# light_sensor_basic.net
KiCad netlist of a schematic drawn in EAGLE
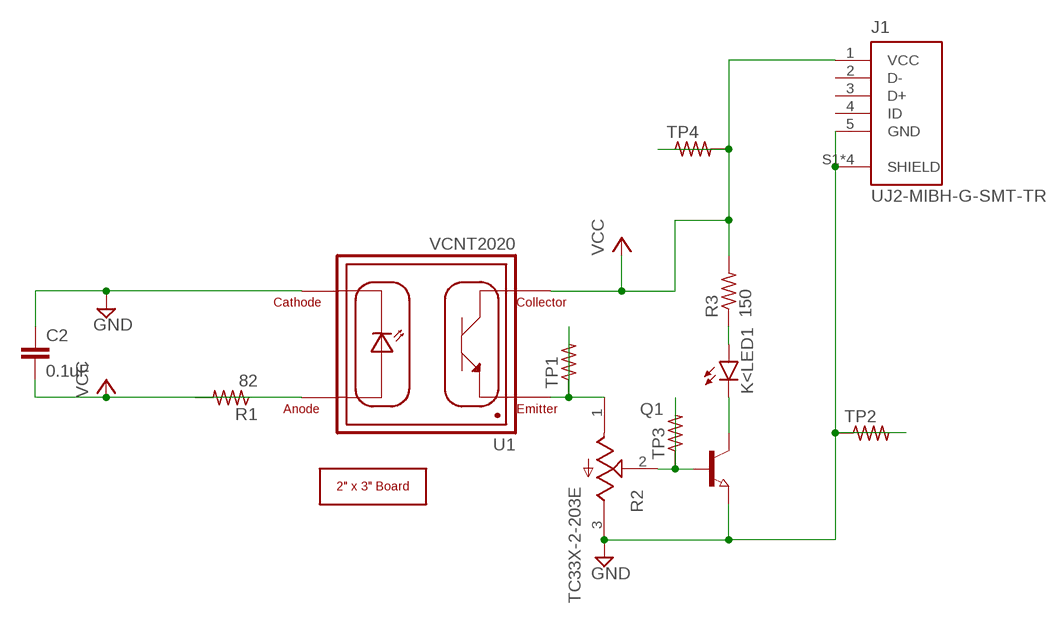
[diagram p0: schematic, sheet 1]

(export (version "E")
  (design (tool "Eeschema 10.0.6"))
  (components
    (comp (ref "C2")
      (value "0.1uF")
      (footprint "eagle-import:C1206")
      (libsource (lib "eagle-import") (part "C-EUC1206"))
    )
    (comp (ref "J1")
      (value "UJ2-MIBH-G-SMT-TR")
      (footprint "eagle-import:CUI_UJ2-MIBH-G-SMT-TR")
      (fields (field (name "MANUFACTURER") "CUI"))
      (libsource (lib "eagle-import") (part "UJ2-MIBH-G-SMT-TR"))
    )
    (comp (ref "K<LED1")
      (value "LEDCHIPLED_0805")
      (footprint "eagle-import:CHIPLED_0805")
      (libsource (lib "eagle-import") (part "LEDCHIPLED_0805"))
    )
    (comp (ref "Q1")
      (value "NPN-TRANSISTOR_SOT23")
      (footprint "eagle-import:SOT23")
      (libsource (lib "eagle-import") (part "NPN-TRANSISTOR_SOT23"))
    )
    (comp (ref "R1")
      (value "82")
      (footprint "eagle-import:R1206")
      (libsource (lib "eagle-import") (part "R-US_R1206"))
    )
    (comp (ref "R2")
      (value "TC33X-2-203E")
      (footprint "eagle-import:TRIM_TC33X-2-203E")
      (fields (field (name "DIGIKEY_PART_NUMBER") "TC33X-2-203ETR-ND") (field (name "MF") "Bourns"))
      (libsource (lib "eagle-import") (part "TC33X-2-203E"))
    )
    (comp (ref "R3")
      (value "150")
      (footprint "eagle-import:R0805")
      (libsource (lib "eagle-import") (part "R-US_R0805"))
    )
    (comp (ref "TP1")
      (value "R-US_R1206")
      (footprint "eagle-import:R1206")
      (libsource (lib "eagle-import") (part "R-US_R1206"))
    )
    (comp (ref "TP2")
      (value "R-US_R1206")
      (footprint "eagle-import:R1206")
      (libsource (lib "eagle-import") (part "R-US_R1206"))
    )
    (comp (ref "TP3")
      (value "R-US_R1206")
      (footprint "eagle-import:R1206")
      (libsource (lib "eagle-import") (part "R-US_R1206"))
    )
    (comp (ref "TP4")
      (value "R-US_R1206")
      (footprint "eagle-import:R1206")
      (libsource (lib "eagle-import") (part "R-US_R1206"))
    )
    (comp (ref "U$1")
      (value "2X3_BOARD_V2")
      (footprint "eagle-import:2X3_BOARD_V2")
      (libsource (lib "eagle-import") (part "2X3_BOARD_V2"))
    )
    (comp (ref "U1")
      (value "VCNT2020")
      (footprint "eagle-import:XDCR_VCNT2020")
      (fields (field (name "DIGIKEY_PART_NUMBER") "VCNT2020TR-ND") (field (name "MF") "Vishay"))
      (libsource (lib "eagle-import") (part "VCNT2020"))
    )
  )
  (nets
    (net (code "1") (name "GND") (class "Default")
      (node (ref "C2") (pin "1") (pinfunction "1_1") (pintype "passive"))
      (node (ref "J1") (pin "5") (pinfunction "GND_5") (pintype "power_in"))
      (node (ref "J1") (pin "S1") (pinfunction "SHIELD_S1") (pintype "passive"))
      (node (ref "J1") (pin "S2") (pinfunction "SHIELD_S2") (pintype "passive"))
      (node (ref "J1") (pin "S3") (pinfunction "SHIELD_S3") (pintype "passive"))
      (node (ref "J1") (pin "S4") (pinfunction "SHIELD_S4") (pintype "passive"))
      (node (ref "Q1") (pin "2") (pinfunction "E_2") (pintype "passive"))
      (node (ref "R2") (pin "3") (pinfunction "CW_3") (pintype "passive"))
      (node (ref "TP2") (pin "1") (pinfunction "1_1") (pintype "passive"))
      (node (ref "TP2") (pin "2") (pinfunction "2_2") (pintype "passive"))
      (node (ref "U1") (pin "4") (pinfunction "CATHODE_4") (pintype "passive"))
    )
    (net (code "2") (name "Net-(K<LED1-PadA)") (class "Default")
      (node (ref "K<LED1") (pin "A") (pinfunction "A_A") (pintype "passive"))
      (node (ref "R3") (pin "1") (pinfunction "1_1") (pintype "passive"))
    )
    (net (code "3") (name "Net-(Q1-B)") (class "Default")
      (node (ref "Q1") (pin "1") (pinfunction "B_1") (pintype "passive"))
      (node (ref "R2") (pin "2") (pinfunction "W_2") (pintype "passive"))
      (node (ref "TP3") (pin "1") (pinfunction "1_1") (pintype "passive"))
      (node (ref "TP3") (pin "2") (pinfunction "2_2") (pintype "passive"))
    )
    (net (code "4") (name "Net-(Q1-C)") (class "Default")
      (node (ref "K<LED1") (pin "C") (pinfunction "C_C") (pintype "passive"))
      (node (ref "Q1") (pin "3") (pinfunction "C_3") (pintype "passive"))
    )
    (net (code "5") (name "Net-(R2-CCW)") (class "Default")
      (node (ref "R2") (pin "1") (pinfunction "CCW_1") (pintype "passive"))
      (node (ref "TP1") (pin "1") (pinfunction "1_1") (pintype "passive"))
      (node (ref "TP1") (pin "2") (pinfunction "2_2") (pintype "passive"))
      (node (ref "U1") (pin "1") (pinfunction "EMITTER_1") (pintype "passive"))
    )
    (net (code "6") (name "Net-(U1-ANODE)") (class "Default")
      (node (ref "R1") (pin "2") (pinfunction "2_2") (pintype "passive"))
      (node (ref "U1") (pin "3") (pinfunction "ANODE_3") (pintype "passive"))
    )
    (net (code "7") (name "VCC") (class "Default")
      (node (ref "C2") (pin "2") (pinfunction "2_2") (pintype "passive"))
      (node (ref "J1") (pin "1") (pinfunction "VCC_1") (pintype "power_in"))
      (node (ref "R1") (pin "1") (pinfunction "1_1") (pintype "passive"))
      (node (ref "R3") (pin "2") (pinfunction "2_2") (pintype "passive"))
      (node (ref "TP4") (pin "1") (pinfunction "1_1") (pintype "passive"))
      (node (ref "TP4") (pin "2") (pinfunction "2_2") (pintype "passive"))
      (node (ref "U1") (pin "2") (pinfunction "COLLECTOR_2") (pintype "passive"))
    )
    (net (code "8") (name "unconnected-(J1-D+-Pad3)") (class "Default")
      (node (ref "J1") (pin "3") (pinfunction "D+_3") (pintype "bidirectional"))
    )
    (net (code "9") (name "unconnected-(J1-D--Pad2)") (class "Default")
      (node (ref "J1") (pin "2") (pinfunction "D-_2") (pintype "bidirectional"))
    )
    (net (code "10") (name "unconnected-(J1-ID-Pad4)") (class "Default")
      (node (ref "J1") (pin "4") (pinfunction "ID_4") (pintype "bidirectional"))
    )
  )
)
